# SAMV71_Xplained_Ultra_Power_Multiplexer.net
KiCad netlist of a schematic drawn in Altium Designer
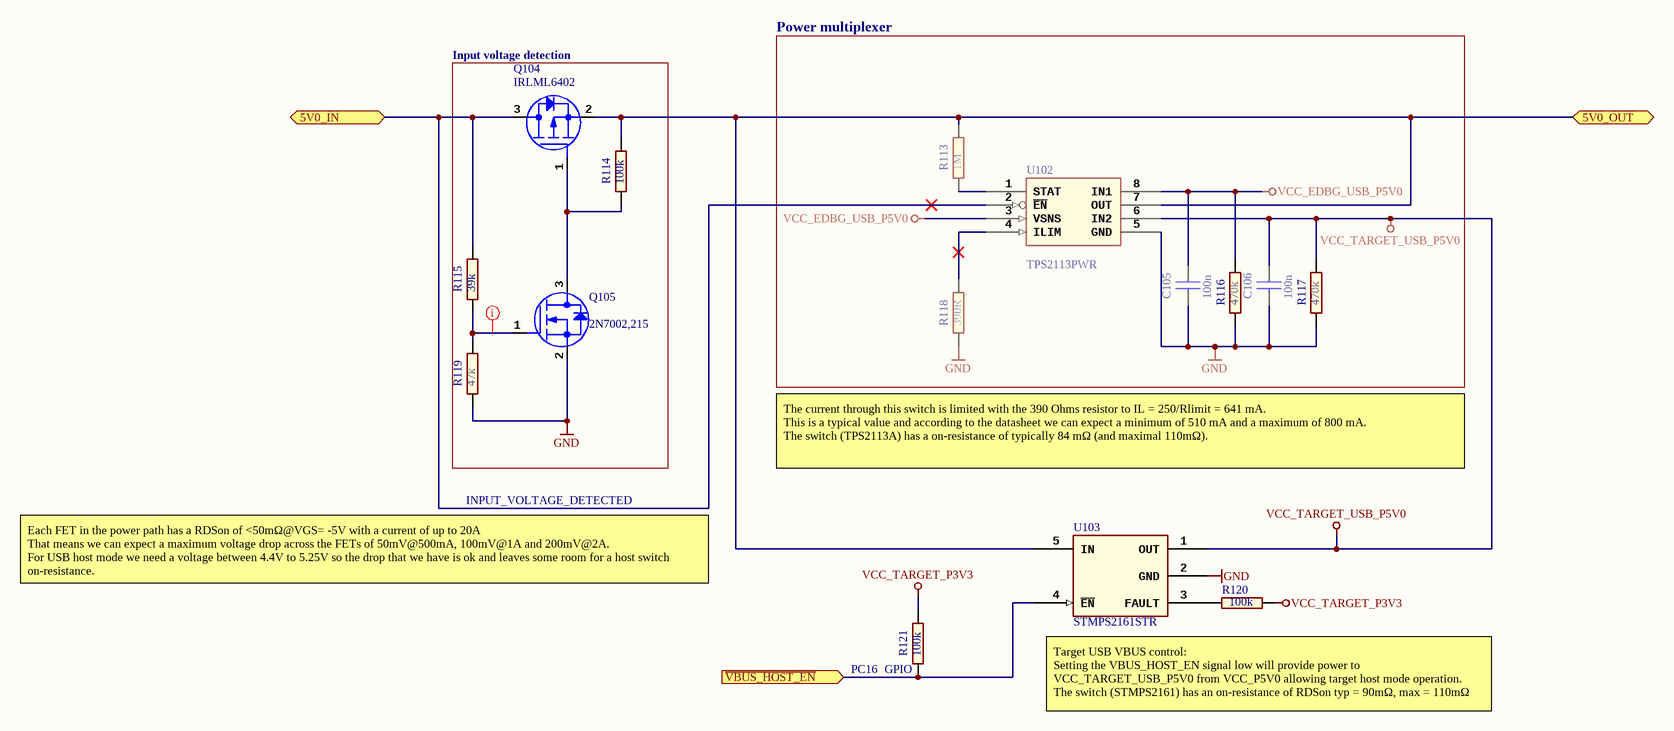
[diagram p0: SAMV71_Xplained_Ultra_Power_Multiplexer.SchDoc]

(export (version "E")
  (design (tool "Eeschema 10.0.6"))
  (components
    (comp (ref "C105")
      (value "100n")
      (footprint "AP1-00001")
      (description "Ceramic capacitor, SMD 0402, X7R, 16V, +/-10%")
      (fields (field (name "TOLERANCE") "16V, +/-10%") (field (name "MANUFACTURER") "Kemet"))
      (libsource (lib "AltiumDbLib") (part "CAP-NONPOL"))
    )
    (comp (ref "C106")
      (value "100n")
      (footprint "AP1-00001")
      (description "Ceramic capacitor, SMD 0402, X7R, 16V, +/-10%")
      (fields (field (name "TOLERANCE") "16V, +/-10%") (field (name "MANUFACTURER") "Kemet"))
      (libsource (lib "AltiumDbLib") (part "CAP-NONPOL"))
    )
    (comp (ref "Q104")
      (value "IRLML6402")
      (footprint "AP5-00002")
      (description "P-ch. MOSFET. -30V, -3.7A continuous,RDS(ON)=0.05Ohm@VGS=-4,5V, RDS(ON)=0.08Ohm@VGS=-2.5V")
      (fields (field (name "MANUFACTURER") "International Rectifier") (field (name "MPN") "IRLML6402PBF"))
      (libsource (lib "AltiumDbLib") (part "MOSFET_P_GSD"))
    )
    (comp (ref "Q105")
      (value "2N7002,215")
      (footprint "AP5-00002")
      (description "N-Channel MOSFET. 60V, 0.300A continuous, 1.2A Peak. RDS(ON) = 3.8Ohm@VGS=4.5V, VGS(th)<2.5V")
      (fields (field (name "MANUFACTURER") "NXP"))
      (libsource (lib "AltiumDbLib") (part "MOSFET_N_GSD"))
    )
    (comp (ref "R113")
      (value "1M")
      (footprint "AP2-00000")
      (description "Thick film resistor, SMD 0402, 1/16W, 1%")
      (fields (field (name "TOLERANCE") "1 %") (field (name "MANUFACTURER") "ASJ"))
      (libsource (lib "AltiumDbLib") (part "R2"))
    )
    (comp (ref "R114")
      (value "100k")
      (footprint "AP2-00000")
      (description "Thick film resistor, SMD 0402, 1/16W, 1%")
      (fields (field (name "TOLERANCE") "1 %") (field (name "MANUFACTURER") "ASJ"))
      (libsource (lib "AltiumDbLib") (part "R2"))
    )
    (comp (ref "R115")
      (value "39k")
      (footprint "AP2-00000")
      (description "Thick film resistor, SMD 0402, 1/16W, 1%")
      (fields (field (name "TOLERANCE") "1 %") (field (name "MANUFACTURER") "ASJ"))
      (libsource (lib "AltiumDbLib") (part "R2"))
    )
    (comp (ref "R116")
      (value "470k")
      (footprint "AP2-00000")
      (description "Thick film resistor, SMD 0402, 1/16W, 1%")
      (fields (field (name "TOLERANCE") "1 %") (field (name "MANUFACTURER") "ASJ"))
      (libsource (lib "AltiumDbLib") (part "R2"))
    )
    (comp (ref "R117")
      (value "470k")
      (footprint "AP2-00000")
      (description "Thick film resistor, SMD 0402, 1/16W, 1%")
      (fields (field (name "TOLERANCE") "1 %") (field (name "MANUFACTURER") "ASJ"))
      (libsource (lib "AltiumDbLib") (part "R2"))
    )
    (comp (ref "R118")
      (value "390R")
      (footprint "AP2-00000")
      (description "Thick film resistor, SMD 0402, 1/16W, 1%")
      (fields (field (name "TOLERANCE") "1 %") (field (name "MANUFACTURER") "ASJ"))
      (libsource (lib "AltiumDbLib") (part "R2"))
    )
    (comp (ref "R119")
      (value "47k")
      (footprint "AP2-00000")
      (description "Thick film resistor, SMD 0402, 1/16W, 1%")
      (fields (field (name "TOLERANCE") "1 %") (field (name "MANUFACTURER") "KOA"))
      (libsource (lib "AltiumDbLib") (part "R2"))
    )
    (comp (ref "R120")
      (value "100k")
      (footprint "AP2-00011")
      (description "Thick film resistor, SMD 0402, 1/16W, 1%")
      (fields (field (name "TOLERANCE") "1 %") (field (name "MANUFACTURER") "ASJ"))
      (libsource (lib "") (part "R2_1"))
    )
    (comp (ref "R121")
      (value "100k")
      (footprint "AP2-00011")
      (description "Thick film resistor, SMD 0402, 1/16W, 1%")
      (fields (field (name "TOLERANCE") "1 %") (field (name "MANUFACTURER") "ASJ"))
      (libsource (lib "AltiumDbLib") (part "R2"))
    )
    (comp (ref "U102")
      (value "TPS2113PWR")
      (footprint "AP6-00054")
      (description "Autoswitching 2:1 Power Mux")
      (fields (field (name "MANUFACTURER") "Texas Instruments"))
      (libsource (lib "AltiumDbLib") (part "TPS2112"))
    )
    (comp (ref "U103")
      (value "STMPS2161STR")
      (footprint "AP6-00087")
      (description "Single channel power switch, 1A, reverse block, active low enabled.")
      (fields (field (name "TOLERANCE") "2.7 to 5.5V") (field (name "MANUFACTURER") "ST"))
      (libsource (lib "AltiumDbLib") (part "STMPS2161"))
    )
  )
  (nets
    (net (code "1") (name "/5V0_IN") (class "Default")
      (node (ref "Q104") (pin "3") (pinfunction "D_3") (pintype "passive"))
      (node (ref "R115") (pin "2") (pinfunction "2_2") (pintype "passive"))
      (node (ref "U102") (pin "2") (pinfunction "~{EN}_2") (pintype "input"))
    )
    (net (code "2") (name "/5V0_OUT") (class "Default")
      (node (ref "Q104") (pin "2") (pinfunction "S_2") (pintype "passive"))
      (node (ref "R113") (pin "2") (pinfunction "2_2") (pintype "passive"))
      (node (ref "R114") (pin "2") (pinfunction "2_2") (pintype "passive"))
      (node (ref "U102") (pin "7") (pinfunction "OUT_7") (pintype "power_in"))
      (node (ref "U103") (pin "5") (pinfunction "IN_5") (pintype "power_in"))
    )
    (net (code "3") (name "/~{VBUS_HOST_EN}") (class "Default")
      (node (ref "R121") (pin "1") (pinfunction "1_1") (pintype "passive"))
      (node (ref "U103") (pin "4") (pinfunction "~{EN}_4") (pintype "input"))
    )
    (net (code "4") (name "GND") (class "Default")
      (node (ref "C105") (pin "2") (pinfunction "2_2") (pintype "passive"))
      (node (ref "C106") (pin "2") (pinfunction "2_2") (pintype "passive"))
      (node (ref "Q105") (pin "2") (pinfunction "S_2") (pintype "passive"))
      (node (ref "R116") (pin "1") (pinfunction "1_1") (pintype "passive"))
      (node (ref "R117") (pin "1") (pinfunction "1_1") (pintype "passive"))
      (node (ref "R118") (pin "1") (pinfunction "1_1") (pintype "passive"))
      (node (ref "R119") (pin "1") (pinfunction "1_1") (pintype "passive"))
      (node (ref "U102") (pin "5") (pinfunction "GND_5") (pintype "power_in"))
      (node (ref "U103") (pin "2") (pinfunction "GND_2") (pintype "power_in"))
    )
    (net (code "5") (name "Net-(Q104-G)") (class "Default")
      (node (ref "Q104") (pin "1") (pinfunction "G_1") (pintype "passive"))
      (node (ref "Q105") (pin "3") (pinfunction "D_3") (pintype "passive"))
      (node (ref "R114") (pin "1") (pinfunction "1_1") (pintype "passive"))
    )
    (net (code "6") (name "Net-(Q105-G)") (class "Default")
      (node (ref "Q105") (pin "1") (pinfunction "G_1") (pintype "passive"))
      (node (ref "R115") (pin "1") (pinfunction "1_1") (pintype "passive"))
      (node (ref "R119") (pin "2") (pinfunction "2_2") (pintype "passive"))
    )
    (net (code "7") (name "Net-(U102-ILIM)") (class "Default")
      (node (ref "R118") (pin "2") (pinfunction "2_2") (pintype "passive"))
      (node (ref "U102") (pin "4") (pinfunction "ILIM_4") (pintype "input"))
    )
    (net (code "8") (name "Net-(U102-STAT)") (class "Default")
      (node (ref "R113") (pin "1") (pinfunction "1_1") (pintype "passive"))
      (node (ref "U102") (pin "1") (pinfunction "STAT_1") (pintype "open_collector"))
    )
    (net (code "9") (name "Net-(U103-FAULT)") (class "Default")
      (node (ref "R120") (pin "2") (pinfunction "2_2") (pintype "passive"))
      (node (ref "U103") (pin "3") (pinfunction "FAULT_3") (pintype "open_collector"))
    )
    (net (code "10") (name "VCC_EDBG_USB_P5V0") (class "Default")
      (node (ref "C105") (pin "1") (pinfunction "1_1") (pintype "passive"))
      (node (ref "R116") (pin "2") (pinfunction "2_2") (pintype "passive"))
      (node (ref "U102") (pin "3") (pinfunction "VSNS_3") (pintype "input"))
      (node (ref "U102") (pin "8") (pinfunction "IN1_8") (pintype "power_in"))
    )
    (net (code "11") (name "VCC_TARGET_P3V3") (class "Default")
      (node (ref "R120") (pin "1") (pinfunction "1_1") (pintype "passive"))
      (node (ref "R121") (pin "2") (pinfunction "2_2") (pintype "passive"))
    )
    (net (code "12") (name "VCC_TARGET_USB_P5V0") (class "Default")
      (node (ref "C106") (pin "1") (pinfunction "1_1") (pintype "passive"))
      (node (ref "R117") (pin "2") (pinfunction "2_2") (pintype "passive"))
      (node (ref "U102") (pin "6") (pinfunction "IN2_6") (pintype "power_in"))
      (node (ref "U103") (pin "1") (pinfunction "OUT_1") (pintype "power_in"))
    )
  )
)
